# Microcontroller.net
KiCad netlist of a schematic drawn in Altium Designer
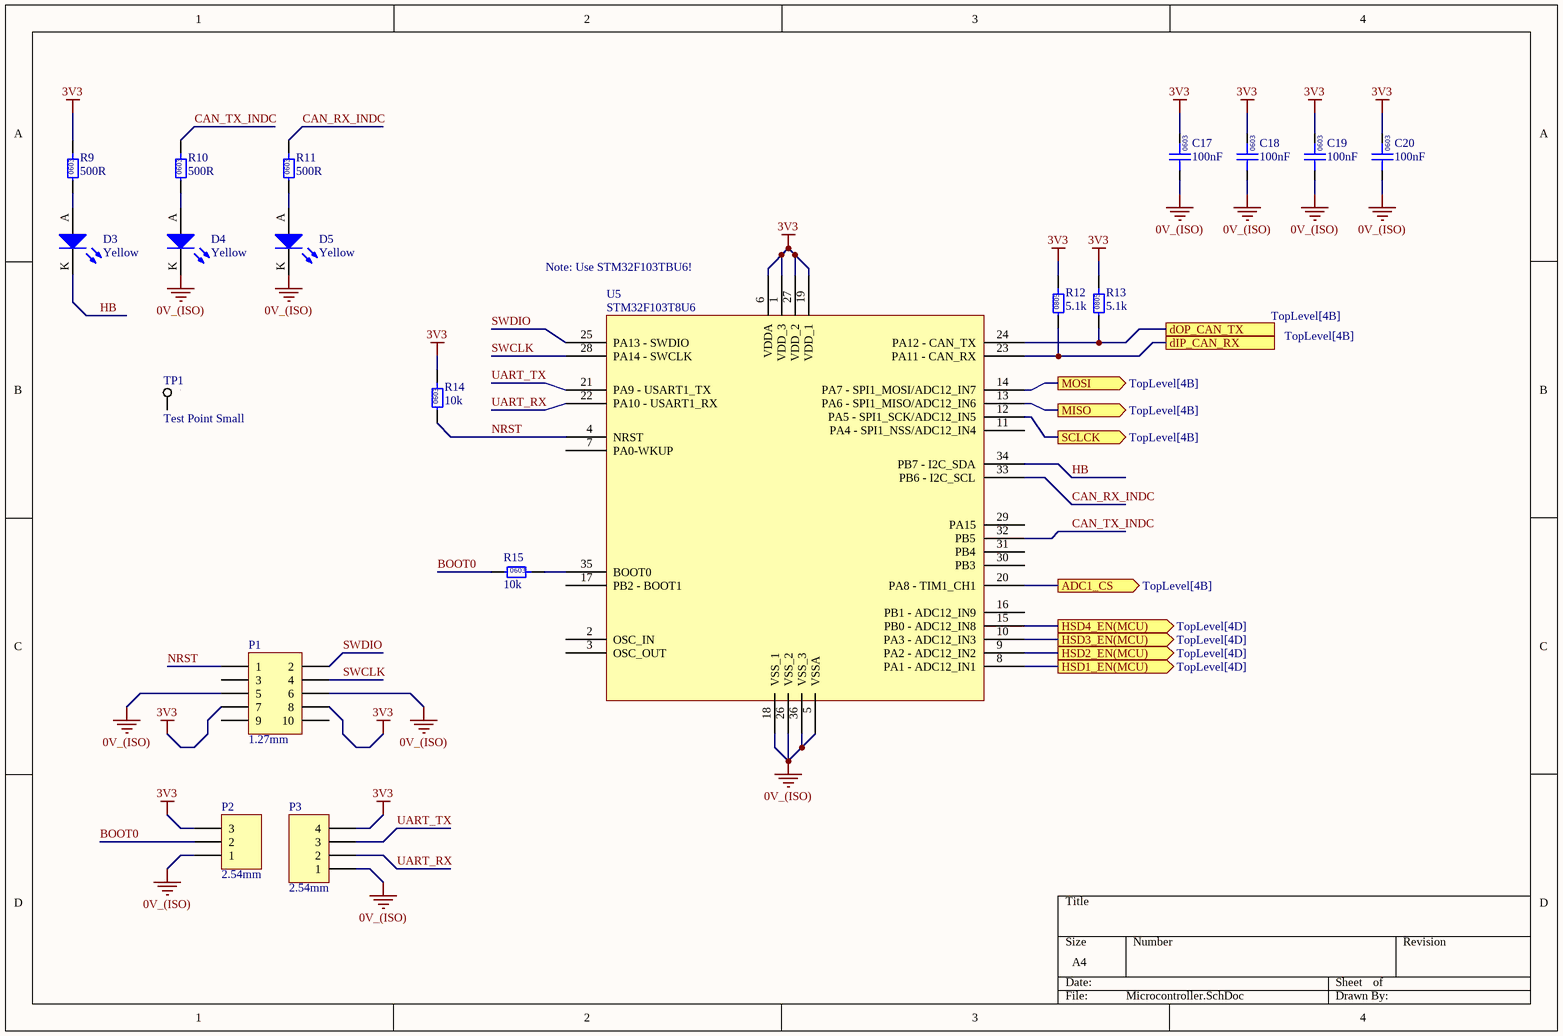
[diagram p0: Microcontroller.SchDoc]

(export (version "E")
  (design (tool "Eeschema 10.0.6"))
  (components
    (comp (ref "C17")
      (value "100nF")
      (footprint "0603")
      (fields
        (field (name "PART NUMBER") "GCM188L81H104KA57D")
        (field (name "MANUFACTURER") "muRata")
        (field (name "TOLERANCE") "±10%")
      )
      (libsource (lib "ts_standard_library") (part "Capacitor 0603"))
    )
    (comp (ref "C18")
      (value "100nF")
      (footprint "0603")
      (fields
        (field (name "PART NUMBER") "GCM188L81H104KA57D")
        (field (name "MANUFACTURER") "muRata")
        (field (name "TOLERANCE") "±10%")
      )
      (libsource (lib "ts_standard_library") (part "Capacitor 0603"))
    )
    (comp (ref "C19")
      (value "100nF")
      (footprint "0603")
      (fields
        (field (name "PART NUMBER") "GCM188L81H104KA57D")
        (field (name "MANUFACTURER") "muRata")
        (field (name "TOLERANCE") "±10%")
      )
      (libsource (lib "ts_standard_library") (part "Capacitor 0603"))
    )
    (comp (ref "C20")
      (value "100nF")
      (footprint "0603")
      (fields
        (field (name "PART NUMBER") "GCM188L81H104KA57D")
        (field (name "MANUFACTURER") "muRata")
        (field (name "TOLERANCE") "±10%")
      )
      (libsource (lib "ts_standard_library") (part "Capacitor 0603"))
    )
    (comp (ref "D3")
      (value "Yellow")
      (footprint "0805 LED")
      (description "Yellow LED Indication - Discrete 1.75V 0805 (2012 Metric)")
      (fields (field (name "PART NUMBER") "SML-211YTT86") (field (name "MANUFACTURER") "ROHM Semiconductor"))
      (libsource (lib "ts_standard_library") (part "LED"))
    )
    (comp (ref "D4")
      (value "Yellow")
      (footprint "0805 LED")
      (description "Yellow LED Indication - Discrete 1.75V 0805 (2012 Metric)")
      (fields (field (name "PART NUMBER") "SML-211YTT86") (field (name "MANUFACTURER") "ROHM Semiconductor"))
      (libsource (lib "ts_standard_library") (part "LED"))
    )
    (comp (ref "D5")
      (value "Yellow")
      (footprint "0805 LED")
      (description "Yellow LED Indication - Discrete 1.75V 0805 (2012 Metric)")
      (fields (field (name "PART NUMBER") "SML-211YTT86") (field (name "MANUFACTURER") "ROHM Semiconductor"))
      (libsource (lib "ts_standard_library") (part "LED"))
    )
    (comp (ref "P1")
      (value "1.27mm")
      (footprint "3221-10-0300-00")
      (fields
        (field (name "PART NUMBER") "SMD 1.27mm Header 2x5 (3221-10-0300-00)")
        (field (name "CONTACT") "NA")
      )
      (libsource (lib "ts_standard_connectors") (part "Header 2x5"))
    )
    (comp (ref "P2")
      (value "2.54mm")
      (footprint "TH 2.54mm Header 1x3")
      (fields (field (name "PART NUMBER") "TH 2.54mm Header 1x3") (field (name "CONTACT") "NA"))
      (libsource (lib "ts_standard_connectors") (part "Header 1x3"))
    )
    (comp (ref "P3")
      (value "2.54mm")
      (footprint "TH 2.54mm Header 1x4")
      (fields (field (name "PART NUMBER") "TH 2.54mm Header 1x4") (field (name "CONTACT") "NA"))
      (libsource (lib "ts_standard_connectors") (part "Header 1x4"))
    )
    (comp (ref "R9")
      (value "500R")
      (footprint "0603")
      (fields
        (field (name "PART NUMBER") "RT0603BRD07500RL")
        (field (name "MANUFACTURER") "YAGEO")
        (field (name "TOLERANCE") "0.01")
      )
      (libsource (lib "ts_standard_library") (part "Resistor 0603"))
    )
    (comp (ref "R10")
      (value "500R")
      (footprint "0603")
      (fields
        (field (name "PART NUMBER") "RT0603BRD07500RL")
        (field (name "MANUFACTURER") "YAGEO")
        (field (name "TOLERANCE") "0.01")
      )
      (libsource (lib "ts_standard_library") (part "Resistor 0603"))
    )
    (comp (ref "R11")
      (value "500R")
      (footprint "0603")
      (fields
        (field (name "PART NUMBER") "RT0603BRD07500RL")
        (field (name "MANUFACTURER") "YAGEO")
        (field (name "TOLERANCE") "0.01")
      )
      (libsource (lib "ts_standard_library") (part "Resistor 0603"))
    )
    (comp (ref "R12")
      (value "5.1k")
      (footprint "0805")
      (fields
        (field (name "PART NUMBER") "RC0805FR075K1L")
        (field (name "MANUFACTURER") "YAGEO")
        (field (name "TOLERANCE") "0.01")
      )
      (libsource (lib "ts_standard_library") (part "Resistor 0805"))
    )
    (comp (ref "R13")
      (value "5.1k")
      (footprint "0805")
      (fields
        (field (name "PART NUMBER") "RC0805FR075K1L")
        (field (name "MANUFACTURER") "YAGEO")
        (field (name "TOLERANCE") "0.01")
      )
      (libsource (lib "ts_standard_library") (part "Resistor 0805"))
    )
    (comp (ref "R14")
      (value "10k")
      (footprint "0603")
      (fields
        (field (name "PART NUMBER") "RC0603FR-0710KL")
        (field (name "MANUFACTURER") "YAGEO")
        (field (name "TOLERANCE") "0.01")
      )
      (libsource (lib "ts_standard_library") (part "Resistor 0603"))
    )
    (comp (ref "R15")
      (value "10k")
      (footprint "0603")
      (fields
        (field (name "PART NUMBER") "RC0603FR-0710KL")
        (field (name "MANUFACTURER") "YAGEO")
        (field (name "TOLERANCE") "0.01")
      )
      (libsource (lib "ts_standard_library") (part "Resistor 0603"))
    )
    (comp (ref "TP1")
      (value "Test Point Small")
      (footprint "SMD Test Point 1mm")
      (fields (field (name "PART NUMBER") "SMD Test Point Small") (field (name "CONTACT") "NA"))
      (libsource (lib "ts_standard_connectors") (part "Test Point Small"))
    )
    (comp (ref "U5")
      (value "STM32F103T8U6")
      (footprint "STM_QFN-36")
      (description "ARM® Cortex®-M3 STM32F1 Microcontroller IC 32-Bit 72MHz 64KB (64K x 8) FLASH QFN")
      (fields (field (name "MANUFACTURER") "ST Microelectronics"))
      (libsource (lib "ts_standard_library") (part "STM32F103T8U6"))
    )
  )
  (nets
    (net (code "1") (name "/ADC1_CS") (class "Default")
      (node (ref "U5") (pin "20") (pinfunction "PA8_-_TIM1_CH1_20") (pintype "passive"))
    )
    (net (code "2") (name "/BOOT0") (class "Default")
      (node (ref "P2") (pin "2") (pinfunction "2_2") (pintype "passive"))
      (node (ref "R15") (pin "1") (pinfunction "1_1") (pintype "passive"))
    )
    (net (code "3") (name "/CAN_RX_INDC") (class "Default")
      (node (ref "R11") (pin "2") (pinfunction "2_2") (pintype "passive"))
      (node (ref "U5") (pin "33") (pinfunction "PB6_-_I2C_SCL_33") (pintype "passive"))
    )
    (net (code "4") (name "/CAN_TX_INDC") (class "Default")
      (node (ref "R10") (pin "2") (pinfunction "2_2") (pintype "passive"))
      (node (ref "U5") (pin "32") (pinfunction "PB5_32") (pintype "passive"))
    )
    (net (code "5") (name "/HB") (class "Default")
      (node (ref "D3") (pin "K") (pinfunction "K_K") (pintype "passive"))
      (node (ref "U5") (pin "34") (pinfunction "PB7_-_I2C_SDA_34") (pintype "passive"))
    )
    (net (code "6") (name "/HSD1_EN(MCU)") (class "Default")
      (node (ref "U5") (pin "8") (pinfunction "PA1_-_ADC12_IN1_8") (pintype "passive"))
    )
    (net (code "7") (name "/HSD2_EN(MCU)") (class "Default")
      (node (ref "U5") (pin "9") (pinfunction "PA2_-_ADC12_IN2_9") (pintype "passive"))
    )
    (net (code "8") (name "/HSD3_EN(MCU)") (class "Default")
      (node (ref "U5") (pin "10") (pinfunction "PA3_-_ADC12_IN3_10") (pintype "passive"))
    )
    (net (code "9") (name "/HSD4_EN(MCU)") (class "Default")
      (node (ref "U5") (pin "15") (pinfunction "PB0_-_ADC12_IN8_15") (pintype "passive"))
    )
    (net (code "10") (name "/MISO") (class "Default")
      (node (ref "U5") (pin "13") (pinfunction "PA6_-_SPI1_MISO/ADC12_IN6_13") (pintype "passive"))
    )
    (net (code "11") (name "/MOSI") (class "Default")
      (node (ref "U5") (pin "14") (pinfunction "PA7_-_SPI1_MOSI/ADC12_IN7_14") (pintype "passive"))
    )
    (net (code "12") (name "/NRST") (class "Default")
      (node (ref "P1") (pin "1") (pinfunction "1_1") (pintype "passive"))
      (node (ref "R14") (pin "1") (pinfunction "1_1") (pintype "passive"))
      (node (ref "U5") (pin "4") (pinfunction "NRST_4") (pintype "passive"))
    )
    (net (code "13") (name "/SCLCK") (class "Default")
      (node (ref "U5") (pin "12") (pinfunction "PA5_-_SPI1_SCK/ADC12_IN5_12") (pintype "passive"))
    )
    (net (code "14") (name "/SWCLK") (class "Default")
      (node (ref "P1") (pin "4") (pinfunction "4_4") (pintype "passive"))
      (node (ref "U5") (pin "28") (pinfunction "PA14_-_SWCLK_28") (pintype "passive"))
    )
    (net (code "15") (name "/SWDIO") (class "Default")
      (node (ref "P1") (pin "2") (pinfunction "2_2") (pintype "passive"))
      (node (ref "U5") (pin "25") (pinfunction "PA13_-_SWDIO_25") (pintype "passive"))
    )
    (net (code "16") (name "/UART_RX") (class "Default")
      (node (ref "P3") (pin "2") (pinfunction "2_2") (pintype "passive"))
      (node (ref "U5") (pin "22") (pinfunction "PA10_-_USART1_RX_22") (pintype "passive"))
    )
    (net (code "17") (name "/UART_TX") (class "Default")
      (node (ref "P3") (pin "3") (pinfunction "3_3") (pintype "passive"))
      (node (ref "U5") (pin "21") (pinfunction "PA9_-_USART1_TX_21") (pintype "passive"))
    )
    (net (code "18") (name "/dIP_CAN_RX") (class "Default")
      (node (ref "R12") (pin "1") (pinfunction "1_1") (pintype "passive"))
      (node (ref "U5") (pin "23") (pinfunction "PA11_-_CAN_RX_23") (pintype "passive"))
    )
    (net (code "19") (name "/dOP_CAN_TX") (class "Default")
      (node (ref "R13") (pin "1") (pinfunction "1_1") (pintype "passive"))
      (node (ref "U5") (pin "24") (pinfunction "PA12_-_CAN_TX_24") (pintype "passive"))
    )
    (net (code "20") (name "0V_(ISO)") (class "Default")
      (node (ref "C17") (pin "1") (pinfunction "1_1") (pintype "passive"))
      (node (ref "C18") (pin "1") (pinfunction "1_1") (pintype "passive"))
      (node (ref "C19") (pin "1") (pinfunction "1_1") (pintype "passive"))
      (node (ref "C20") (pin "1") (pinfunction "1_1") (pintype "passive"))
      (node (ref "D4") (pin "K") (pinfunction "K_K") (pintype "passive"))
      (node (ref "D5") (pin "K") (pinfunction "K_K") (pintype "passive"))
      (node (ref "P1") (pin "5") (pinfunction "5_5") (pintype "passive"))
      (node (ref "P1") (pin "6") (pinfunction "6_6") (pintype "passive"))
      (node (ref "P2") (pin "1") (pinfunction "1_1") (pintype "passive"))
      (node (ref "P3") (pin "1") (pinfunction "1_1") (pintype "passive"))
      (node (ref "U5") (pin "18") (pinfunction "VSS_1_18") (pintype "passive"))
      (node (ref "U5") (pin "26") (pinfunction "VSS_2_26") (pintype "passive"))
      (node (ref "U5") (pin "36") (pinfunction "VSS_3_36") (pintype "passive"))
      (node (ref "U5") (pin "5") (pinfunction "VSSA_5") (pintype "passive"))
    )
    (net (code "21") (name "3V3") (class "Default")
      (node (ref "C17") (pin "2") (pinfunction "2_2") (pintype "passive"))
      (node (ref "C18") (pin "2") (pinfunction "2_2") (pintype "passive"))
      (node (ref "C19") (pin "2") (pinfunction "2_2") (pintype "passive"))
      (node (ref "C20") (pin "2") (pinfunction "2_2") (pintype "passive"))
      (node (ref "P1") (pin "7") (pinfunction "7_7") (pintype "passive"))
      (node (ref "P1") (pin "8") (pinfunction "8_8") (pintype "passive"))
      (node (ref "P2") (pin "3") (pinfunction "3_3") (pintype "passive"))
      (node (ref "P3") (pin "4") (pinfunction "4_4") (pintype "passive"))
      (node (ref "R12") (pin "2") (pinfunction "2_2") (pintype "passive"))
      (node (ref "R13") (pin "2") (pinfunction "2_2") (pintype "passive"))
      (node (ref "R14") (pin "2") (pinfunction "2_2") (pintype "passive"))
      (node (ref "R9") (pin "2") (pinfunction "2_2") (pintype "passive"))
      (node (ref "U5") (pin "1") (pinfunction "VDD_3_1") (pintype "passive"))
      (node (ref "U5") (pin "19") (pinfunction "VDD_1_19") (pintype "passive"))
      (node (ref "U5") (pin "27") (pinfunction "VDD_2_27") (pintype "passive"))
      (node (ref "U5") (pin "6") (pinfunction "VDDA_6") (pintype "passive"))
    )
    (net (code "22") (name "Net-(D3-PadA)") (class "Default")
      (node (ref "D3") (pin "A") (pinfunction "A_A") (pintype "passive"))
      (node (ref "R9") (pin "1") (pinfunction "1_1") (pintype "passive"))
    )
    (net (code "23") (name "Net-(D4-PadA)") (class "Default")
      (node (ref "D4") (pin "A") (pinfunction "A_A") (pintype "passive"))
      (node (ref "R10") (pin "1") (pinfunction "1_1") (pintype "passive"))
    )
    (net (code "24") (name "Net-(D5-PadA)") (class "Default")
      (node (ref "D5") (pin "A") (pinfunction "A_A") (pintype "passive"))
      (node (ref "R11") (pin "1") (pinfunction "1_1") (pintype "passive"))
    )
    (net (code "25") (name "Net-(U5-BOOT0)") (class "Default")
      (node (ref "R15") (pin "2") (pinfunction "2_2") (pintype "passive"))
      (node (ref "U5") (pin "35") (pinfunction "BOOT0_35") (pintype "passive"))
    )
    (net (code "26") (name "unconnected-(P1-Pad3)") (class "Default")
      (node (ref "P1") (pin "3") (pinfunction "3_3") (pintype "passive"))
    )
    (net (code "27") (name "unconnected-(P1-Pad9)") (class "Default")
      (node (ref "P1") (pin "9") (pinfunction "9_9") (pintype "passive"))
    )
    (net (code "28") (name "unconnected-(P1-Pad10)") (class "Default")
      (node (ref "P1") (pin "10") (pinfunction "10_10") (pintype "passive"))
    )
    (net (code "29") (name "unconnected-(TP1-Pad1)") (class "Default")
      (node (ref "TP1") (pin "1") (pinfunction "1_1") (pintype "passive"))
    )
    (net (code "30") (name "unconnected-(U5-OSC_IN-Pad2)") (class "Default")
      (node (ref "U5") (pin "2") (pinfunction "OSC_IN_2") (pintype "passive"))
    )
    (net (code "31") (name "unconnected-(U5-OSC_OUT-Pad3)") (class "Default")
      (node (ref "U5") (pin "3") (pinfunction "OSC_OUT_3") (pintype "passive"))
    )
    (net (code "32") (name "unconnected-(U5-PA0-WKUP-Pad7)") (class "Default")
      (node (ref "U5") (pin "7") (pinfunction "PA0-WKUP_7") (pintype "passive"))
    )
    (net (code "33") (name "unconnected-(U5-PA4_-_SPI1_NSS{slash}ADC12_IN4-Pad11)") (class "Default")
      (node (ref "U5") (pin "11") (pinfunction "PA4_-_SPI1_NSS/ADC12_IN4_11") (pintype "passive"))
    )
    (net (code "34") (name "unconnected-(U5-PA15-Pad29)") (class "Default")
      (node (ref "U5") (pin "29") (pinfunction "PA15_29") (pintype "passive"))
    )
    (net (code "35") (name "unconnected-(U5-PB1_-_ADC12_IN9-Pad16)") (class "Default")
      (node (ref "U5") (pin "16") (pinfunction "PB1_-_ADC12_IN9_16") (pintype "passive"))
    )
    (net (code "36") (name "unconnected-(U5-PB2_-_BOOT1-Pad17)") (class "Default")
      (node (ref "U5") (pin "17") (pinfunction "PB2_-_BOOT1_17") (pintype "passive"))
    )
    (net (code "37") (name "unconnected-(U5-PB3-Pad30)") (class "Default")
      (node (ref "U5") (pin "30") (pinfunction "PB3_30") (pintype "passive"))
    )
    (net (code "38") (name "unconnected-(U5-PB4-Pad31)") (class "Default")
      (node (ref "U5") (pin "31") (pinfunction "PB4_31") (pintype "passive"))
    )
  )
)
